# Drinks_MotorDriver-v0_3.net
KiCad netlist of a schematic drawn in EAGLE
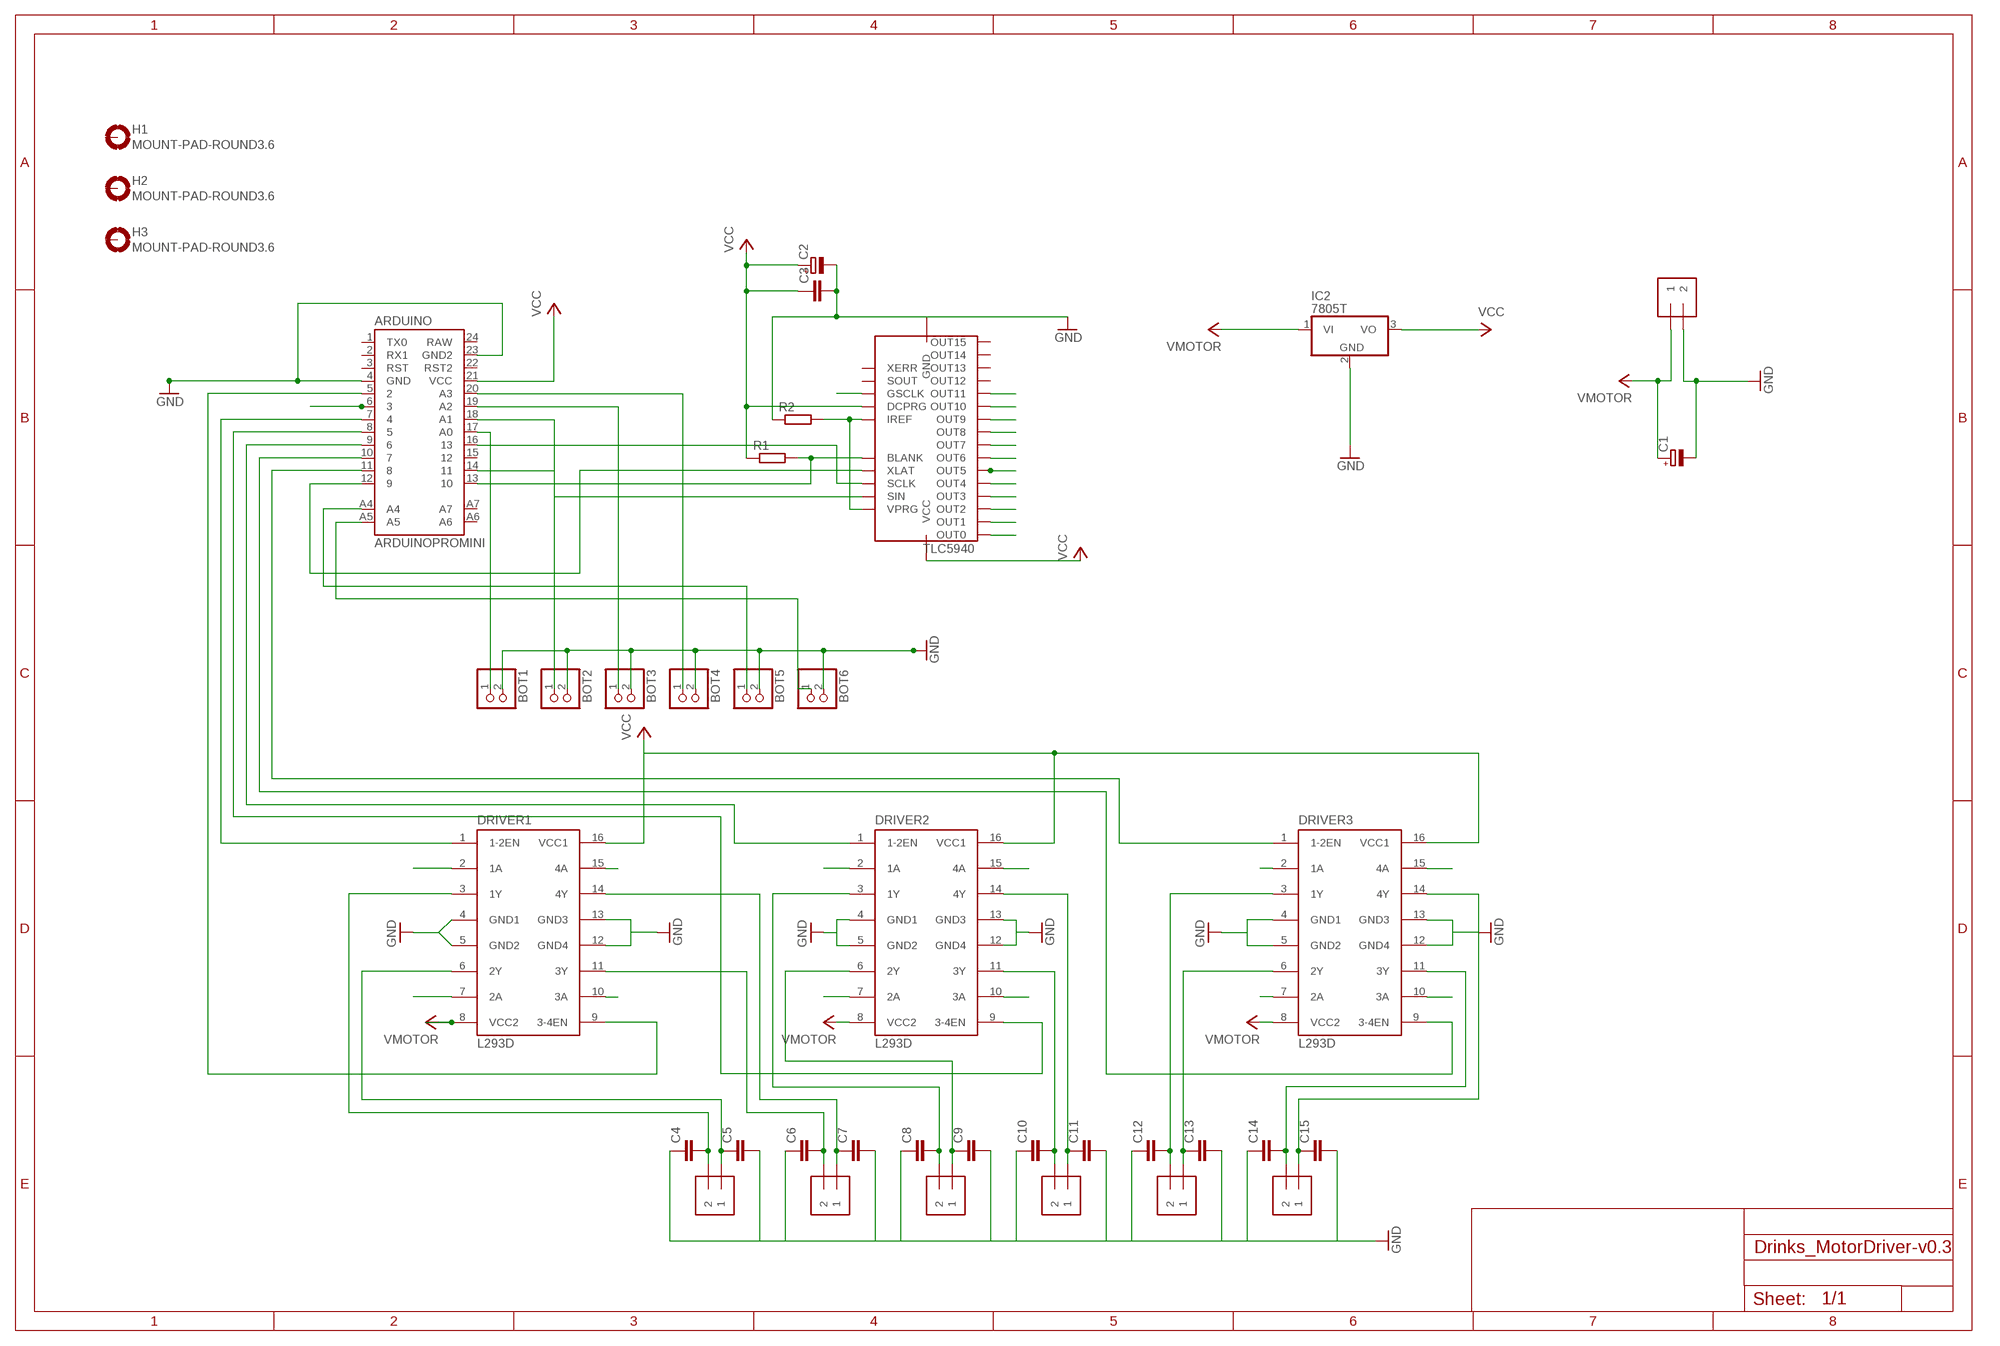
[diagram p0: schematic, sheet 1]

(export (version "E")
  (design (tool "Eeschema 10.0.6"))
  (components
    (comp (ref "ARDUINO")
      (value "ARDUINOPROMINI")
      (footprint "eagle-import:ARDUINO_PRO_MINI")
      (libsource (lib "eagle-import") (part "ARDUINO_PRO_MINI"))
    )
    (comp (ref "BOT1")
      (value "JST_2PIN-THM")
      (footprint "eagle-import:JST-PH-2-THM")
      (libsource (lib "eagle-import") (part "JST_2PIN-THM"))
    )
    (comp (ref "BOT2")
      (value "JST_2PIN-THM")
      (footprint "eagle-import:JST-PH-2-THM")
      (libsource (lib "eagle-import") (part "JST_2PIN-THM"))
    )
    (comp (ref "BOT3")
      (value "JST_2PIN-THM")
      (footprint "eagle-import:JST-PH-2-THM")
      (libsource (lib "eagle-import") (part "JST_2PIN-THM"))
    )
    (comp (ref "BOT4")
      (value "JST_2PIN-THM")
      (footprint "eagle-import:JST-PH-2-THM")
      (libsource (lib "eagle-import") (part "JST_2PIN-THM"))
    )
    (comp (ref "BOT5")
      (value "JST_2PIN-THM")
      (footprint "eagle-import:JST-PH-2-THM")
      (libsource (lib "eagle-import") (part "JST_2PIN-THM"))
    )
    (comp (ref "BOT6")
      (value "JST_2PIN-THM")
      (footprint "eagle-import:JST-PH-2-THM")
      (libsource (lib "eagle-import") (part "JST_2PIN-THM"))
    )
    (comp (ref "C1")
      (value "CPOL-EUE5-8.5")
      (footprint "eagle-import:E5-8,5")
      (libsource (lib "eagle-import") (part "CPOL-EUE5-8.5"))
    )
    (comp (ref "C2")
      (value "CPOL-EUE5-8.5")
      (footprint "eagle-import:E5-8,5")
      (libsource (lib "eagle-import") (part "CPOL-EUE5-8.5"))
    )
    (comp (ref "C3")
      (value "C-EU025-025X050")
      (footprint "eagle-import:C025-025X050")
      (libsource (lib "eagle-import") (part "C-EU025-025X050"))
    )
    (comp (ref "C4")
      (value "C-EU025-025X050")
      (footprint "eagle-import:C025-025X050")
      (libsource (lib "eagle-import") (part "C-EU025-025X050"))
    )
    (comp (ref "C5")
      (value "C-EU025-025X050")
      (footprint "eagle-import:C025-025X050")
      (libsource (lib "eagle-import") (part "C-EU025-025X050"))
    )
    (comp (ref "C6")
      (value "C-EU025-025X050")
      (footprint "eagle-import:C025-025X050")
      (libsource (lib "eagle-import") (part "C-EU025-025X050"))
    )
    (comp (ref "C7")
      (value "C-EU025-025X050")
      (footprint "eagle-import:C025-025X050")
      (libsource (lib "eagle-import") (part "C-EU025-025X050"))
    )
    (comp (ref "C8")
      (value "C-EU025-025X050")
      (footprint "eagle-import:C025-025X050")
      (libsource (lib "eagle-import") (part "C-EU025-025X050"))
    )
    (comp (ref "C9")
      (value "C-EU025-025X050")
      (footprint "eagle-import:C025-025X050")
      (libsource (lib "eagle-import") (part "C-EU025-025X050"))
    )
    (comp (ref "C10")
      (value "C-EU025-025X050")
      (footprint "eagle-import:C025-025X050")
      (libsource (lib "eagle-import") (part "C-EU025-025X050"))
    )
    (comp (ref "C11")
      (value "C-EU025-025X050")
      (footprint "eagle-import:C025-025X050")
      (libsource (lib "eagle-import") (part "C-EU025-025X050"))
    )
    (comp (ref "C12")
      (value "C-EU025-025X050")
      (footprint "eagle-import:C025-025X050")
      (libsource (lib "eagle-import") (part "C-EU025-025X050"))
    )
    (comp (ref "C13")
      (value "C-EU025-025X050")
      (footprint "eagle-import:C025-025X050")
      (libsource (lib "eagle-import") (part "C-EU025-025X050"))
    )
    (comp (ref "C14")
      (value "C-EU025-025X050")
      (footprint "eagle-import:C025-025X050")
      (libsource (lib "eagle-import") (part "C-EU025-025X050"))
    )
    (comp (ref "C15")
      (value "C-EU025-025X050")
      (footprint "eagle-import:C025-025X050")
      (libsource (lib "eagle-import") (part "C-EU025-025X050"))
    )
    (comp (ref "DRIVER1")
      (value "L293D")
      (footprint "eagle-import:DIL16")
      (libsource (lib "eagle-import") (part "L293D"))
    )
    (comp (ref "DRIVER2")
      (value "L293D")
      (footprint "eagle-import:DIL16")
      (libsource (lib "eagle-import") (part "L293D"))
    )
    (comp (ref "DRIVER3")
      (value "L293D")
      (footprint "eagle-import:DIL16")
      (libsource (lib "eagle-import") (part "L293D"))
    )
    (comp (ref "H1")
      (value "MOUNT-PAD-ROUND3.6")
      (footprint "eagle-import:3,6-PAD")
      (libsource (lib "eagle-import") (part "MOUNT-PAD-ROUND3.6"))
    )
    (comp (ref "H2")
      (value "MOUNT-PAD-ROUND3.6")
      (footprint "eagle-import:3,6-PAD")
      (libsource (lib "eagle-import") (part "MOUNT-PAD-ROUND3.6"))
    )
    (comp (ref "H3")
      (value "MOUNT-PAD-ROUND3.6")
      (footprint "eagle-import:3,6-PAD")
      (libsource (lib "eagle-import") (part "MOUNT-PAD-ROUND3.6"))
    )
    (comp (ref "IC2")
      (value "7805T")
      (footprint "eagle-import:TO220H")
      (libsource (lib "eagle-import") (part "78T05"))
    )
    (comp (ref "MOT1")
      (value "1X2-3.5MM")
      (footprint "eagle-import:1X2-3.5MM")
      (libsource (lib "eagle-import") (part "1X2-3.5MM"))
    )
    (comp (ref "MOT2")
      (value "1X2-3.5MM")
      (footprint "eagle-import:1X2-3.5MM")
      (libsource (lib "eagle-import") (part "1X2-3.5MM"))
    )
    (comp (ref "MOT3")
      (value "1X2-3.5MM")
      (footprint "eagle-import:1X2-3.5MM")
      (libsource (lib "eagle-import") (part "1X2-3.5MM"))
    )
    (comp (ref "MOT4")
      (value "1X2-3.5MM")
      (footprint "eagle-import:1X2-3.5MM")
      (libsource (lib "eagle-import") (part "1X2-3.5MM"))
    )
    (comp (ref "MOT5")
      (value "1X2-3.5MM")
      (footprint "eagle-import:1X2-3.5MM")
      (libsource (lib "eagle-import") (part "1X2-3.5MM"))
    )
    (comp (ref "MOT6")
      (value "1X2-3.5MM")
      (footprint "eagle-import:1X2-3.5MM")
      (libsource (lib "eagle-import") (part "1X2-3.5MM"))
    )
    (comp (ref "R1")
      (value "R-EU_0204/7")
      (footprint "eagle-import:0204_7")
      (libsource (lib "eagle-import") (part "R-EU_0204/7"))
    )
    (comp (ref "R2")
      (value "R-EU_0204/7")
      (footprint "eagle-import:0204_7")
      (libsource (lib "eagle-import") (part "R-EU_0204/7"))
    )
    (comp (ref "TLC5940")
      (value "IC-PACKAGE_DIL28-4")
      (footprint "eagle-import:IC-PACKAGE_DIL28-4")
      (libsource (lib "eagle-import") (part "IC-PACKAGE_DIL28-4"))
    )
    (comp (ref "VIN")
      (value "1X2-3.5MM")
      (footprint "eagle-import:1X2-3.5MM")
      (libsource (lib "eagle-import") (part "1X2-3.5MM"))
    )
  )
  (nets
    (net (code "1") (name "/GSCLK") (class "Default")
      (node (ref "ARDUINO") (pin "6") (pinfunction "3_6") (pintype "bidirectional"))
      (node (ref "TLC5940") (pin "18") (pinfunction "GSCLK_18") (pintype "input"))
    )
    (net (code "2") (name "/MOT1A") (class "Default")
      (node (ref "DRIVER1") (pin "2") (pinfunction "1A_2") (pintype "input"))
      (node (ref "TLC5940") (pin "28") (pinfunction "OUT0_28") (pintype "open_collector"))
    )
    (net (code "3") (name "/MOT1B") (class "Default")
      (node (ref "DRIVER1") (pin "7") (pinfunction "2A_7") (pintype "input"))
      (node (ref "TLC5940") (pin "1") (pinfunction "OUT1_1") (pintype "open_collector"))
    )
    (net (code "4") (name "/MOT2A") (class "Default")
      (node (ref "DRIVER1") (pin "10") (pinfunction "3A_10") (pintype "input"))
      (node (ref "TLC5940") (pin "2") (pinfunction "OUT2_2") (pintype "open_collector"))
    )
    (net (code "5") (name "/MOT2B") (class "Default")
      (node (ref "DRIVER1") (pin "15") (pinfunction "4A_15") (pintype "input"))
      (node (ref "TLC5940") (pin "3") (pinfunction "OUT3_3") (pintype "open_collector"))
    )
    (net (code "6") (name "/MOT3A") (class "Default")
      (node (ref "DRIVER2") (pin "2") (pinfunction "1A_2") (pintype "input"))
      (node (ref "TLC5940") (pin "4") (pinfunction "OUT4_4") (pintype "open_collector"))
    )
    (net (code "7") (name "/MOT3B") (class "Default")
      (node (ref "DRIVER2") (pin "7") (pinfunction "2A_7") (pintype "input"))
      (node (ref "TLC5940") (pin "5") (pinfunction "OUT5_5") (pintype "open_collector"))
    )
    (net (code "8") (name "/MOT4A") (class "Default")
      (node (ref "DRIVER2") (pin "10") (pinfunction "3A_10") (pintype "input"))
      (node (ref "TLC5940") (pin "6") (pinfunction "OUT6_6") (pintype "open_collector"))
    )
    (net (code "9") (name "/MOT4B") (class "Default")
      (node (ref "DRIVER2") (pin "15") (pinfunction "4A_15") (pintype "input"))
      (node (ref "TLC5940") (pin "7") (pinfunction "OUT7_7") (pintype "open_collector"))
    )
    (net (code "10") (name "/MOT5A") (class "Default")
      (node (ref "DRIVER3") (pin "2") (pinfunction "1A_2") (pintype "input"))
      (node (ref "TLC5940") (pin "8") (pinfunction "OUT8_8") (pintype "open_collector"))
    )
    (net (code "11") (name "/MOT5B") (class "Default")
      (node (ref "DRIVER3") (pin "7") (pinfunction "2A_7") (pintype "input"))
      (node (ref "TLC5940") (pin "9") (pinfunction "OUT9_9") (pintype "open_collector"))
    )
    (net (code "12") (name "/MOT6A") (class "Default")
      (node (ref "DRIVER3") (pin "10") (pinfunction "3A_10") (pintype "input"))
      (node (ref "TLC5940") (pin "10") (pinfunction "OUT10_10") (pintype "open_collector"))
    )
    (net (code "13") (name "/MOT6B") (class "Default")
      (node (ref "DRIVER3") (pin "15") (pinfunction "4A_15") (pintype "input"))
      (node (ref "TLC5940") (pin "11") (pinfunction "OUT11_11") (pintype "open_collector"))
    )
    (net (code "14") (name "GND") (class "Default")
      (node (ref "ARDUINO") (pin "23") (pinfunction "GND2_23") (pintype "bidirectional"))
      (node (ref "ARDUINO") (pin "4") (pinfunction "GND_4") (pintype "bidirectional"))
      (node (ref "BOT1") (pin "2") (pinfunction "1_2") (pintype "passive"))
      (node (ref "BOT2") (pin "2") (pinfunction "1_2") (pintype "passive"))
      (node (ref "BOT3") (pin "2") (pinfunction "1_2") (pintype "passive"))
      (node (ref "BOT4") (pin "2") (pinfunction "1_2") (pintype "passive"))
      (node (ref "BOT5") (pin "2") (pinfunction "1_2") (pintype "passive"))
      (node (ref "BOT6") (pin "2") (pinfunction "1_2") (pintype "passive"))
      (node (ref "C1") (pin "-") (pinfunction "-_-") (pintype "passive"))
      (node (ref "C10") (pin "1") (pinfunction "1_1") (pintype "passive"))
      (node (ref "C11") (pin "2") (pinfunction "2_2") (pintype "passive"))
      (node (ref "C12") (pin "1") (pinfunction "1_1") (pintype "passive"))
      (node (ref "C13") (pin "2") (pinfunction "2_2") (pintype "passive"))
      (node (ref "C14") (pin "1") (pinfunction "1_1") (pintype "passive"))
      (node (ref "C15") (pin "2") (pinfunction "2_2") (pintype "passive"))
      (node (ref "C2") (pin "-") (pinfunction "-_-") (pintype "passive"))
      (node (ref "C3") (pin "2") (pinfunction "2_2") (pintype "passive"))
      (node (ref "C4") (pin "1") (pinfunction "1_1") (pintype "passive"))
      (node (ref "C5") (pin "2") (pinfunction "2_2") (pintype "passive"))
      (node (ref "C6") (pin "1") (pinfunction "1_1") (pintype "passive"))
      (node (ref "C7") (pin "2") (pinfunction "2_2") (pintype "passive"))
      (node (ref "C8") (pin "1") (pinfunction "1_1") (pintype "passive"))
      (node (ref "C9") (pin "2") (pinfunction "2_2") (pintype "passive"))
      (node (ref "DRIVER1") (pin "12") (pinfunction "GND4_12") (pintype "power_in"))
      (node (ref "DRIVER1") (pin "13") (pinfunction "GND3_13") (pintype "power_in"))
      (node (ref "DRIVER1") (pin "4") (pinfunction "GND1_4") (pintype "power_in"))
      (node (ref "DRIVER1") (pin "5") (pinfunction "GND2_5") (pintype "power_in"))
      (node (ref "DRIVER2") (pin "12") (pinfunction "GND4_12") (pintype "power_in"))
      (node (ref "DRIVER2") (pin "13") (pinfunction "GND3_13") (pintype "power_in"))
      (node (ref "DRIVER2") (pin "4") (pinfunction "GND1_4") (pintype "power_in"))
      (node (ref "DRIVER2") (pin "5") (pinfunction "GND2_5") (pintype "power_in"))
      (node (ref "DRIVER3") (pin "12") (pinfunction "GND4_12") (pintype "power_in"))
      (node (ref "DRIVER3") (pin "13") (pinfunction "GND3_13") (pintype "power_in"))
      (node (ref "DRIVER3") (pin "4") (pinfunction "GND1_4") (pintype "power_in"))
      (node (ref "DRIVER3") (pin "5") (pinfunction "GND2_5") (pintype "power_in"))
      (node (ref "IC2") (pin "2") (pinfunction "GND_2") (pintype "passive"))
      (node (ref "R2") (pin "1") (pinfunction "1_1") (pintype "passive"))
      (node (ref "TLC5940") (pin "22") (pinfunction "GND_22") (pintype "power_in"))
      (node (ref "VIN") (pin "2") (pinfunction "2_2") (pintype "passive"))
    )
    (net (code "15") (name "Net-(ARDUINO-2)") (class "Default")
      (node (ref "ARDUINO") (pin "5") (pinfunction "2_5") (pintype "bidirectional"))
      (node (ref "DRIVER1") (pin "9") (pinfunction "3-4EN_9") (pintype "input"))
    )
    (net (code "16") (name "Net-(ARDUINO-4)") (class "Default")
      (node (ref "ARDUINO") (pin "7") (pinfunction "4_7") (pintype "bidirectional"))
      (node (ref "DRIVER1") (pin "1") (pinfunction "1-2EN_1") (pintype "input"))
    )
    (net (code "17") (name "Net-(ARDUINO-5)") (class "Default")
      (node (ref "ARDUINO") (pin "8") (pinfunction "5_8") (pintype "bidirectional"))
      (node (ref "DRIVER2") (pin "9") (pinfunction "3-4EN_9") (pintype "input"))
    )
    (net (code "18") (name "Net-(ARDUINO-6)") (class "Default")
      (node (ref "ARDUINO") (pin "9") (pinfunction "6_9") (pintype "bidirectional"))
      (node (ref "DRIVER2") (pin "1") (pinfunction "1-2EN_1") (pintype "input"))
    )
    (net (code "19") (name "Net-(ARDUINO-7)") (class "Default")
      (node (ref "ARDUINO") (pin "10") (pinfunction "7_10") (pintype "bidirectional"))
      (node (ref "DRIVER3") (pin "9") (pinfunction "3-4EN_9") (pintype "input"))
    )
    (net (code "20") (name "Net-(ARDUINO-8)") (class "Default")
      (node (ref "ARDUINO") (pin "11") (pinfunction "8_11") (pintype "bidirectional"))
      (node (ref "DRIVER3") (pin "1") (pinfunction "1-2EN_1") (pintype "input"))
    )
    (net (code "21") (name "Net-(ARDUINO-9)") (class "Default")
      (node (ref "ARDUINO") (pin "12") (pinfunction "9_12") (pintype "bidirectional"))
      (node (ref "TLC5940") (pin "24") (pinfunction "XLAT_24") (pintype "input"))
    )
    (net (code "22") (name "Net-(ARDUINO-10)") (class "Default")
      (node (ref "ARDUINO") (pin "13") (pinfunction "10_13") (pintype "bidirectional"))
      (node (ref "R1") (pin "2") (pinfunction "2_2") (pintype "passive"))
      (node (ref "TLC5940") (pin "23") (pinfunction "BLANK_23") (pintype "input"))
    )
    (net (code "23") (name "Net-(ARDUINO-11)") (class "Default")
      (node (ref "ARDUINO") (pin "14") (pinfunction "11_14") (pintype "bidirectional"))
      (node (ref "TLC5940") (pin "26") (pinfunction "SIN_26") (pintype "input"))
    )
    (net (code "24") (name "Net-(ARDUINO-13)") (class "Default")
      (node (ref "ARDUINO") (pin "16") (pinfunction "13_16") (pintype "bidirectional"))
      (node (ref "TLC5940") (pin "25") (pinfunction "SCLK_25") (pintype "input"))
    )
    (net (code "25") (name "Net-(ARDUINO-A0)") (class "Default")
      (node (ref "ARDUINO") (pin "17") (pinfunction "A0_17") (pintype "bidirectional"))
      (node (ref "BOT1") (pin "1") (pinfunction "2_1") (pintype "passive"))
    )
    (net (code "26") (name "Net-(ARDUINO-A1)") (class "Default")
      (node (ref "ARDUINO") (pin "18") (pinfunction "A1_18") (pintype "bidirectional"))
      (node (ref "BOT2") (pin "1") (pinfunction "2_1") (pintype "passive"))
    )
    (net (code "27") (name "Net-(ARDUINO-A2)") (class "Default")
      (node (ref "ARDUINO") (pin "19") (pinfunction "A2_19") (pintype "bidirectional"))
      (node (ref "BOT3") (pin "1") (pinfunction "2_1") (pintype "passive"))
    )
    (net (code "28") (name "Net-(ARDUINO-A3)") (class "Default")
      (node (ref "ARDUINO") (pin "20") (pinfunction "A3_20") (pintype "bidirectional"))
      (node (ref "BOT4") (pin "1") (pinfunction "2_1") (pintype "passive"))
    )
    (net (code "29") (name "Net-(BOT5-2)") (class "Default")
      (node (ref "ARDUINO") (pin "A4") (pinfunction "A4_A4") (pintype "bidirectional"))
      (node (ref "BOT5") (pin "1") (pinfunction "2_1") (pintype "passive"))
    )
    (net (code "30") (name "Net-(BOT6-2)") (class "Default")
      (node (ref "ARDUINO") (pin "A5") (pinfunction "A5_A5") (pintype "bidirectional"))
      (node (ref "BOT6") (pin "1") (pinfunction "2_1") (pintype "passive"))
    )
    (net (code "31") (name "Net-(DRIVER1-1Y)") (class "Default")
      (node (ref "C4") (pin "2") (pinfunction "2_2") (pintype "passive"))
      (node (ref "DRIVER1") (pin "3") (pinfunction "1Y_3") (pintype "output"))
      (node (ref "MOT1") (pin "2") (pinfunction "2_2") (pintype "passive"))
    )
    (net (code "32") (name "Net-(DRIVER1-2Y)") (class "Default")
      (node (ref "C5") (pin "1") (pinfunction "1_1") (pintype "passive"))
      (node (ref "DRIVER1") (pin "6") (pinfunction "2Y_6") (pintype "output"))
      (node (ref "MOT1") (pin "1") (pinfunction "1_1") (pintype "passive"))
    )
    (net (code "33") (name "Net-(DRIVER1-3Y)") (class "Default")
      (node (ref "C6") (pin "2") (pinfunction "2_2") (pintype "passive"))
      (node (ref "DRIVER1") (pin "11") (pinfunction "3Y_11") (pintype "output"))
      (node (ref "MOT2") (pin "2") (pinfunction "2_2") (pintype "passive"))
    )
    (net (code "34") (name "Net-(DRIVER1-4Y)") (class "Default")
      (node (ref "C7") (pin "1") (pinfunction "1_1") (pintype "passive"))
      (node (ref "DRIVER1") (pin "14") (pinfunction "4Y_14") (pintype "output"))
      (node (ref "MOT2") (pin "1") (pinfunction "1_1") (pintype "passive"))
    )
    (net (code "35") (name "Net-(DRIVER2-1Y)") (class "Default")
      (node (ref "C8") (pin "2") (pinfunction "2_2") (pintype "passive"))
      (node (ref "DRIVER2") (pin "3") (pinfunction "1Y_3") (pintype "output"))
      (node (ref "MOT3") (pin "2") (pinfunction "2_2") (pintype "passive"))
    )
    (net (code "36") (name "Net-(DRIVER2-2Y)") (class "Default")
      (node (ref "C9") (pin "1") (pinfunction "1_1") (pintype "passive"))
      (node (ref "DRIVER2") (pin "6") (pinfunction "2Y_6") (pintype "output"))
      (node (ref "MOT3") (pin "1") (pinfunction "1_1") (pintype "passive"))
    )
    (net (code "37") (name "Net-(DRIVER2-3Y)") (class "Default")
      (node (ref "C10") (pin "2") (pinfunction "2_2") (pintype "passive"))
      (node (ref "DRIVER2") (pin "11") (pinfunction "3Y_11") (pintype "output"))
      (node (ref "MOT4") (pin "2") (pinfunction "2_2") (pintype "passive"))
    )
    (net (code "38") (name "Net-(DRIVER2-4Y)") (class "Default")
      (node (ref "C11") (pin "1") (pinfunction "1_1") (pintype "passive"))
      (node (ref "DRIVER2") (pin "14") (pinfunction "4Y_14") (pintype "output"))
      (node (ref "MOT4") (pin "1") (pinfunction "1_1") (pintype "passive"))
    )
    (net (code "39") (name "Net-(DRIVER3-1Y)") (class "Default")
      (node (ref "C12") (pin "2") (pinfunction "2_2") (pintype "passive"))
      (node (ref "DRIVER3") (pin "3") (pinfunction "1Y_3") (pintype "output"))
      (node (ref "MOT5") (pin "2") (pinfunction "2_2") (pintype "passive"))
    )
    (net (code "40") (name "Net-(DRIVER3-2Y)") (class "Default")
      (node (ref "C13") (pin "1") (pinfunction "1_1") (pintype "passive"))
      (node (ref "DRIVER3") (pin "6") (pinfunction "2Y_6") (pintype "output"))
      (node (ref "MOT5") (pin "1") (pinfunction "1_1") (pintype "passive"))
    )
    (net (code "41") (name "Net-(DRIVER3-3Y)") (class "Default")
      (node (ref "C14") (pin "2") (pinfunction "2_2") (pintype "passive"))
      (node (ref "DRIVER3") (pin "11") (pinfunction "3Y_11") (pintype "output"))
      (node (ref "MOT6") (pin "2") (pinfunction "2_2") (pintype "passive"))
    )
    (net (code "42") (name "Net-(DRIVER3-4Y)") (class "Default")
      (node (ref "C15") (pin "1") (pinfunction "1_1") (pintype "passive"))
      (node (ref "DRIVER3") (pin "14") (pinfunction "4Y_14") (pintype "output"))
      (node (ref "MOT6") (pin "1") (pinfunction "1_1") (pintype "passive"))
    )
    (net (code "43") (name "Net-(TLC5940-IREF)") (class "Default")
      (node (ref "R2") (pin "2") (pinfunction "2_2") (pintype "passive"))
      (node (ref "TLC5940") (pin "20") (pinfunction "IREF_20") (pintype "passive"))
      (node (ref "TLC5940") (pin "27") (pinfunction "VPRG_27") (pintype "input"))
    )
    (net (code "44") (name "VCC") (class "Default")
      (node (ref "ARDUINO") (pin "21") (pinfunction "VCC_21") (pintype "bidirectional"))
      (node (ref "C2") (pin "+") (pinfunction "+_+") (pintype "passive"))
      (node (ref "C3") (pin "1") (pinfunction "1_1") (pintype "passive"))
      (node (ref "DRIVER1") (pin "16") (pinfunction "VCC1_16") (pintype "power_in"))
      (node (ref "DRIVER2") (pin "16") (pinfunction "VCC1_16") (pintype "power_in"))
      (node (ref "DRIVER3") (pin "16") (pinfunction "VCC1_16") (pintype "power_in"))
      (node (ref "IC2") (pin "3") (pinfunction "VO_3") (pintype "passive"))
      (node (ref "R1") (pin "1") (pinfunction "1_1") (pintype "passive"))
      (node (ref "TLC5940") (pin "19") (pinfunction "DCPRG_19") (pintype "input"))
      (node (ref "TLC5940") (pin "21") (pinfunction "VCC_21") (pintype "power_in"))
    )
    (net (code "45") (name "VMOTOR") (class "Default")
      (node (ref "C1") (pin "+") (pinfunction "+_+") (pintype "passive"))
      (node (ref "DRIVER1") (pin "8") (pinfunction "VCC2_8") (pintype "power_in"))
      (node (ref "DRIVER2") (pin "8") (pinfunction "VCC2_8") (pintype "power_in"))
      (node (ref "DRIVER3") (pin "8") (pinfunction "VCC2_8") (pintype "power_in"))
      (node (ref "IC2") (pin "1") (pinfunction "VI_1") (pintype "input"))
      (node (ref "VIN") (pin "1") (pinfunction "1_1") (pintype "passive"))
    )
    (net (code "46") (name "unconnected-(ARDUINO-12-Pad15)") (class "Default")
      (node (ref "ARDUINO") (pin "15") (pinfunction "12_15") (pintype "bidirectional"))
    )
    (net (code "47") (name "unconnected-(ARDUINO-PadA6)") (class "Default")
      (node (ref "ARDUINO") (pin "A6") (pinfunction "A6_A6") (pintype "bidirectional"))
    )
    (net (code "48") (name "unconnected-(ARDUINO-PadA7)") (class "Default")
      (node (ref "ARDUINO") (pin "A7") (pinfunction "A7_A7") (pintype "bidirectional"))
    )
    (net (code "49") (name "unconnected-(ARDUINO-RAW-Pad24)") (class "Default")
      (node (ref "ARDUINO") (pin "24") (pinfunction "RAW_24") (pintype "bidirectional"))
    )
    (net (code "50") (name "unconnected-(ARDUINO-RST-Pad3)") (class "Default")
      (node (ref "ARDUINO") (pin "3") (pinfunction "RST_3") (pintype "bidirectional"))
    )
    (net (code "51") (name "unconnected-(ARDUINO-RST2-Pad22)") (class "Default")
      (node (ref "ARDUINO") (pin "22") (pinfunction "RST2_22") (pintype "bidirectional"))
    )
    (net (code "52") (name "unconnected-(ARDUINO-RX1-Pad2)") (class "Default")
      (node (ref "ARDUINO") (pin "2") (pinfunction "RX1_2") (pintype "bidirectional"))
    )
    (net (code "53") (name "unconnected-(ARDUINO-TX0-Pad1)") (class "Default")
      (node (ref "ARDUINO") (pin "1") (pinfunction "TX0_1") (pintype "bidirectional"))
    )
    (net (code "54") (name "unconnected-(H1-MOUNT-PadB3,6)") (class "Default")
      (node (ref "H1") (pin "B3,6") (pinfunction "MOUNT_B3,6") (pintype "passive"))
    )
    (net (code "55") (name "unconnected-(H2-MOUNT-PadB3,6)") (class "Default")
      (node (ref "H2") (pin "B3,6") (pinfunction "MOUNT_B3,6") (pintype "passive"))
    )
    (net (code "56") (name "unconnected-(H3-MOUNT-PadB3,6)") (class "Default")
      (node (ref "H3") (pin "B3,6") (pinfunction "MOUNT_B3,6") (pintype "passive"))
    )
    (net (code "57") (name "unconnected-(TLC5940-OUT12-Pad12)") (class "Default")
      (node (ref "TLC5940") (pin "12") (pinfunction "OUT12_12") (pintype "open_collector"))
    )
    (net (code "58") (name "unconnected-(TLC5940-OUT13-Pad13)") (class "Default")
      (node (ref "TLC5940") (pin "13") (pinfunction "OUT13_13") (pintype "open_collector"))
    )
    (net (code "59") (name "unconnected-(TLC5940-OUT14-Pad14)") (class "Default")
      (node (ref "TLC5940") (pin "14") (pinfunction "OUT14_14") (pintype "open_collector"))
    )
    (net (code "60") (name "unconnected-(TLC5940-OUT15-Pad15)") (class "Default")
      (node (ref "TLC5940") (pin "15") (pinfunction "OUT15_15") (pintype "open_collector"))
    )
    (net (code "61") (name "unconnected-(TLC5940-SOUT-Pad17)") (class "Default")
      (node (ref "TLC5940") (pin "17") (pinfunction "SOUT_17") (pintype "output"))
    )
    (net (code "62") (name "unconnected-(TLC5940-XERR-Pad16)") (class "Default")
      (node (ref "TLC5940") (pin "16") (pinfunction "XERR_16") (pintype "open_collector"))
    )
  )
)
